# CanhBaoChay.net
KiCad netlist of a schematic drawn in Altium Designer
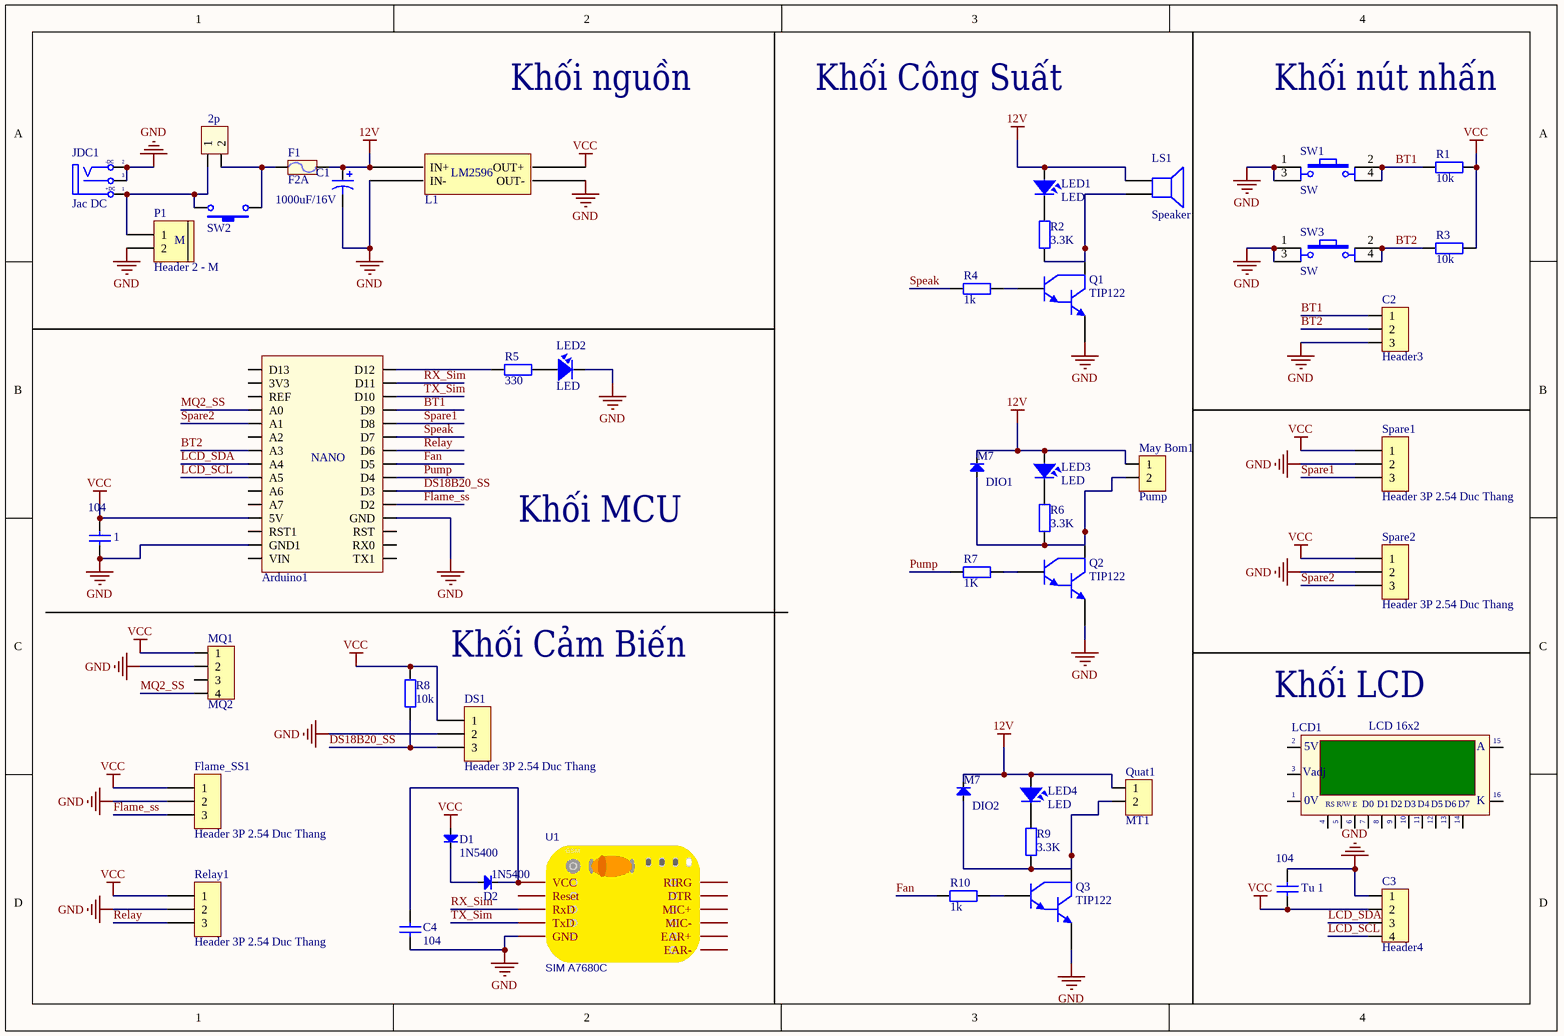
[diagram p0: CanhBaoChay.SchDoc]

(export (version "E")
  (design (tool "Eeschema 10.0.6"))
  (components
    (comp (ref "1")
      (value "104")
      (footprint "C0805")
      (description "Capacitor")
      (fields (field (name "PUBLISHER") "Altium Limited"))
      (libsource (lib "My Library") (part "CapSMD"))
    )
    (comp (ref "Arduino1")
      (value "Arduino Nano")
      (footprint "Arduino Nano")
      (description "Arduino NANO")
      (libsource (lib "My Library") (part "Arduino Nano"))
    )
    (comp (ref "C1")
      (value "1000uF/16V")
      (footprint "C10mm")
      (description "Polarized Capacitor (Axial)")
      (fields (field (name "PUBLISHER") "Altium Limited"))
      (libsource (lib "My Library") (part "Cap Pol 12mm"))
    )
    (comp (ref "C2")
      (value "Header3")
      (footprint "Header3")
      (description "Header IDC, 3 x 1 Pin Vertical 2.54mm Pitch (Non-Boxed, Male)")
      (fields
        (field (name "MANUFACTURER") "Würth Elektronik eiSos GmbH")
        (field (name "PARTNO") "613002143121")
        (field (name "CREATED BY") "Karrer Zheng")
      )
      (libsource (lib "My Library") (part "Header3"))
    )
    (comp (ref "C3")
      (value "Header4")
      (footprint "XH2.54M-4")
      (description "Header IDC, 4 x 1 Pin Vertical 2.54mm Pitch (Non-Boxed, Male)")
      (fields
        (field (name "MANUFACTURER") "Würth Elektronik eiSos GmbH")
        (field (name "PARTNO") "613002143121")
        (field (name "CREATED BY") "Karrer Zheng")
      )
      (libsource (lib "My Library") (part "Header4"))
    )
    (comp (ref "C4")
      (value "104")
      (footprint "C0805")
      (description "Capacitor")
      (fields (field (name "PUBLISHER") "Altium Limited"))
      (libsource (lib "My Library") (part "CapSMD"))
    )
    (comp (ref "D1")
      (value "1N5400")
      (footprint "DIO-5A")
      (description "Default Diode")
      (fields (field (name "PUBLISHER") "Altium Limited"))
      (libsource (lib "My Library") (part "Diode"))
    )
    (comp (ref "D2")
      (value "1N5400")
      (footprint "DIO-5A")
      (description "Default Diode")
      (fields (field (name "PUBLISHER") "Altium Limited"))
      (libsource (lib "My Library") (part "Diode"))
    )
    (comp (ref "DIO1")
      (value "M7")
      (footprint "DIO-SMD-106")
      (description "Default Diode")
      (fields (field (name "PUBLISHER") "Altium Limited"))
      (libsource (lib "My Library (1)") (part "Diode SMD"))
    )
    (comp (ref "DIO2")
      (value "M7")
      (footprint "DIO-SMD-106")
      (description "Default Diode")
      (fields (field (name "PUBLISHER") "Altium Limited"))
      (libsource (lib "My Library (1)") (part "Diode SMD"))
    )
    (comp (ref "DS1")
      (value "Header 3P 2.54 Duc Thang")
      (footprint "Header 3P DC 2.54")
      (description "Cắm")
      (libsource (lib "Header") (part "Header 3P 2.54 Duc Thang"))
    )
    (comp (ref "F1")
      (value "F2A")
      (footprint "Fuse")
      (description "Fuse")
      (fields (field (name "DESIGNED BY") "VanDungEvn"))
      (libsource (lib "My Library") (part "Fuse"))
    )
    (comp (ref "Flame_SS1")
      (value "Header 3P 2.54 Duc Thang")
      (footprint "Header 3P DC 2.54")
      (description "Cắm")
      (libsource (lib "Header") (part "Header 3P 2.54 Duc Thang"))
    )
    (comp (ref "H1")
      (value "2p")
      (footprint "XH2.54M-2")
      (description "Cắm")
      (libsource (lib "Header") (part "Header 2P 2.54 Duc Thang"))
    )
    (comp (ref "JDC1")
      (value "Jac DC")
      (footprint "DC-IN")
      (description "Jac DC input")
      (libsource (lib "My Library") (part "DCIN"))
    )
    (comp (ref "L1")
      (value "BUCK_LM2596")
      (footprint "BUCK_LM2596")
      (libsource (lib "BUCK_LM2596_Sch") (part "BUCK_LM2596"))
    )
    (comp (ref "LCD1")
      (value "LCD 16x2")
      (footprint "LCD16X2N")
      (libsource (lib "My library altium") (part "LCD"))
    )
    (comp (ref "LED1")
      (value "LED")
      (footprint "LED-5 GRe")
      (description "LED Single colour Green and Red")
      (libsource (lib "My Library") (part "LED"))
    )
    (comp (ref "LED2")
      (value "LED")
      (footprint "LED-5 GRe")
      (description "LED Single colour Green and Red")
      (libsource (lib "My Library") (part "LED"))
    )
    (comp (ref "LED3")
      (value "LED")
      (footprint "LED-5 GRe")
      (description "LED Single colour Green and Red")
      (libsource (lib "My Library") (part "LED"))
    )
    (comp (ref "LED4")
      (value "LED")
      (footprint "LED-5 GRe")
      (description "LED Single colour Green and Red")
      (libsource (lib "My Library") (part "LED"))
    )
    (comp (ref "LS1")
      (value "Speaker")
      (footprint "SPEAKER")
      (description "Loudspeaker")
      (fields (field (name "PUBLISHER") "Altium Limited"))
      (libsource (lib "My Library") (part "Speaker"))
    )
    (comp (ref "May Bom1")
      (value "Pump")
      (footprint "Header 2P DC 2.54")
      (description "Header IDC, 2 x 1 Pin Vertical 2.54mm Pitch (Non-Boxed, Male)")
      (fields
        (field (name "MANUFACTURER") "Würth Elektronik eiSos GmbH")
        (field (name "PARTNO") "613002143121")
        (field (name "CREATED BY") "Karrer Zheng")
      )
      (libsource (lib "My Library") (part "Header2"))
    )
    (comp (ref "MQ1")
      (value "MQ2")
      (footprint "Header 4P DC 2.54")
      (description "Header IDC, 4 x 1 Pin Vertical 2.54mm Pitch (Non-Boxed, Male)")
      (fields
        (field (name "MANUFACTURER") "Würth Elektronik eiSos GmbH")
        (field (name "PARTNO") "613002143121")
        (field (name "CREATED BY") "Karrer Zheng")
      )
      (libsource (lib "My Library") (part "Header4"))
    )
    (comp (ref "P1")
      (value "Header 2 - M")
      (footprint "Medium - Header 2")
      (description "Header, 2-Pin, Medium")
      (fields (field (name "PUBLISHER") "Altium Limited"))
      (libsource (lib "My Library") (part "Header 2 - M"))
    )
    (comp (ref "Q1")
      (value "TIP122")
      (footprint "QTO-220")
      (description "Darlington Silicon Power NPN Transistor, 8 Amp, 100 Volts and 65 Watts")
      (libsource (lib "My Library (1)") (part "TIP122"))
    )
    (comp (ref "Q2")
      (value "TIP122")
      (footprint "QTO-220")
      (description "Darlington Silicon Power NPN Transistor, 8 Amp, 100 Volts and 65 Watts")
      (libsource (lib "My Library (1)") (part "TIP122"))
    )
    (comp (ref "Q3")
      (value "TIP122")
      (footprint "QTO-220")
      (description "Darlington Silicon Power NPN Transistor, 8 Amp, 100 Volts and 65 Watts")
      (libsource (lib "My Library (1)") (part "TIP122"))
    )
    (comp (ref "Quat1")
      (value "MT1")
      (footprint "Header 2P DC 2.54")
      (description "Header IDC, 2 x 1 Pin Vertical 2.54mm Pitch (Non-Boxed, Male)")
      (fields
        (field (name "MANUFACTURER") "Würth Elektronik eiSos GmbH")
        (field (name "PARTNO") "613002143121")
        (field (name "CREATED BY") "Karrer Zheng")
      )
      (libsource (lib "My Library") (part "Header2"))
    )
    (comp (ref "R1")
      (value "10k")
      (footprint "RES-SMD-1206")
      (description "Resistor SMD 0805")
      (fields (field (name "PUBLISHER") "Altium Limited"))
      (libsource (lib "") (part "R0805_2"))
    )
    (comp (ref "R2")
      (value "3.3K")
      (footprint "RES-SMD-1206")
      (description "Resistor SMD 0805")
      (fields (field (name "PUBLISHER") "Altium Limited"))
      (libsource (lib "My Library (1)") (part "R0805"))
    )
    (comp (ref "R3")
      (value "10k")
      (footprint "RES-SMD-1206")
      (description "Resistor SMD 0805")
      (fields (field (name "PUBLISHER") "Altium Limited"))
      (libsource (lib "") (part "R0805_2"))
    )
    (comp (ref "R4")
      (value "1k")
      (footprint "RES-SMD-1206")
      (description "Resistor SMD 0805")
      (fields (field (name "PUBLISHER") "Altium Limited"))
      (libsource (lib "") (part "R0805_1"))
    )
    (comp (ref "R5")
      (value "330")
      (footprint "RES-SMD-1206")
      (description "Resistor SMD 0805")
      (fields (field (name "PUBLISHER") "Altium Limited"))
      (libsource (lib "") (part "R0805_1"))
    )
    (comp (ref "R6")
      (value "3.3K")
      (footprint "RES-SMD-1206")
      (description "Resistor SMD 0805")
      (fields (field (name "PUBLISHER") "Altium Limited"))
      (libsource (lib "My Library (1)") (part "R0805"))
    )
    (comp (ref "R7")
      (value "1K")
      (footprint "RES-SMD-1206")
      (description "Resistor SMD 0805")
      (fields (field (name "PUBLISHER") "Altium Limited"))
      (libsource (lib "") (part "R0805_1"))
    )
    (comp (ref "R8")
      (value "10k")
      (footprint "RES-SMD-1206")
      (description "Resistor SMD 0805")
      (fields (field (name "PUBLISHER") "Altium Limited"))
      (libsource (lib "My Library (1)") (part "R0805"))
    )
    (comp (ref "R9")
      (value "3.3K")
      (footprint "RES-SMD-1206")
      (description "Resistor SMD 0805")
      (fields (field (name "PUBLISHER") "Altium Limited"))
      (libsource (lib "My Library (1)") (part "R0805"))
    )
    (comp (ref "R10")
      (value "1k")
      (footprint "RES-SMD-1206")
      (description "Resistor SMD 0805")
      (fields (field (name "PUBLISHER") "Altium Limited"))
      (libsource (lib "") (part "R0805_1"))
    )
    (comp (ref "Relay1")
      (value "Header 3P 2.54 Duc Thang")
      (footprint "XH2.54M-3")
      (description "Cắm")
      (libsource (lib "Header") (part "Header 3P 2.54 Duc Thang"))
    )
    (comp (ref "Spare1")
      (value "Header 3P 2.54 Duc Thang")
      (footprint "XH2.54M-3")
      (description "Cắm")
      (libsource (lib "Header") (part "Header 3P 2.54 Duc Thang"))
    )
    (comp (ref "Spare2")
      (value "Header 3P 2.54 Duc Thang")
      (footprint "XH2.54M-3")
      (description "Cắm")
      (libsource (lib "Header") (part "Header 3P 2.54 Duc Thang"))
    )
    (comp (ref "SW1")
      (value "SW")
      (footprint "SW4")
      (description "Switch button 4 pin")
      (libsource (lib "My Library (1)") (part "SW4"))
    )
    (comp (ref "SW2")
      (value "KCD01-11_SWITCH")
      (footprint "KCD01-11")
      (description "Nut Nhan 2 Chan SMD 3x6x2.5")
      (libsource (lib "KS Chuong") (part "KCD01-11_SWITCH"))
    )
    (comp (ref "SW3")
      (value "SW")
      (footprint "SW4")
      (description "Switch button 4 pin")
      (libsource (lib "My Library (1)") (part "SW4"))
    )
    (comp (ref "Tu 1")
      (value "104")
      (footprint "C0805")
      (description "Capacitor")
      (fields (field (name "PUBLISHER") "Altium Limited"))
      (libsource (lib "My Library") (part "CapSMD"))
    )
    (comp (ref "U1")
      (value "SIM A7680C")
      (footprint "SIM800L MODULE")
      (fields (field (name "BOM_SUPPLIER PART") "B01DLIJM2E") (field (name "CONTRIBUTOR") "trigui"))
      (libsource (lib "Lib_KD") (part "SIM800L"))
    )
  )
  (nets
    (net (code "1") (name "/BT1") (class "Default")
      (node (ref "Arduino1") (pin "D9") (pinfunction "D9_D9") (pintype "passive"))
      (node (ref "C2") (pin "1") (pinfunction "1_1") (pintype "passive"))
      (node (ref "R1") (pin "1") (pinfunction "1_1") (pintype "passive"))
      (node (ref "SW1") (pin "2") (pintype "passive"))
      (node (ref "SW1") (pin "4") (pintype "passive"))
    )
    (net (code "2") (name "/BT2") (class "Default")
      (node (ref "Arduino1") (pin "A3") (pinfunction "A3_A3") (pintype "passive"))
      (node (ref "C2") (pin "2") (pinfunction "2_2") (pintype "passive"))
      (node (ref "R3") (pin "1") (pinfunction "1_1") (pintype "passive"))
      (node (ref "SW3") (pin "2") (pintype "passive"))
      (node (ref "SW3") (pin "4") (pintype "passive"))
    )
    (net (code "3") (name "/DS18B20_SS") (class "Default")
      (node (ref "Arduino1") (pin "D3") (pinfunction "D3_D3") (pintype "passive"))
      (node (ref "DS1") (pin "3") (pinfunction "3_3") (pintype "passive"))
      (node (ref "R8") (pin "2") (pinfunction "2_2") (pintype "passive"))
    )
    (net (code "4") (name "/Fan") (class "Default")
      (node (ref "Arduino1") (pin "D5") (pinfunction "D5_D5") (pintype "passive"))
      (node (ref "R10") (pin "2") (pinfunction "2_2") (pintype "passive"))
    )
    (net (code "5") (name "/Flame_ss") (class "Default")
      (node (ref "Arduino1") (pin "D2") (pinfunction "D2_D2") (pintype "passive"))
      (node (ref "Flame_SS1") (pin "3") (pinfunction "3_3") (pintype "passive"))
    )
    (net (code "6") (name "/LCD_SCL") (class "Default")
      (node (ref "Arduino1") (pin "A5") (pinfunction "A5_A5") (pintype "passive"))
      (node (ref "C3") (pin "4") (pinfunction "4_4") (pintype "passive"))
    )
    (net (code "7") (name "/LCD_SDA") (class "Default")
      (node (ref "Arduino1") (pin "A4") (pinfunction "A4_A4") (pintype "passive"))
      (node (ref "C3") (pin "3") (pinfunction "3_3") (pintype "passive"))
    )
    (net (code "8") (name "/MQ2_SS") (class "Default")
      (node (ref "Arduino1") (pin "A0") (pinfunction "A0_A0") (pintype "passive"))
      (node (ref "MQ1") (pin "4") (pinfunction "4_4") (pintype "passive"))
    )
    (net (code "9") (name "/Pump") (class "Default")
      (node (ref "Arduino1") (pin "D4") (pinfunction "D4_D4") (pintype "passive"))
      (node (ref "R7") (pin "2") (pinfunction "2_2") (pintype "passive"))
    )
    (net (code "10") (name "/RX_Sim") (class "Default")
      (node (ref "Arduino1") (pin "D11") (pinfunction "D11_D11") (pintype "passive"))
      (node (ref "U1") (pin "3") (pinfunction "RxD_3") (pintype "passive"))
    )
    (net (code "11") (name "/Relay") (class "Default")
      (node (ref "Arduino1") (pin "D6") (pinfunction "D6_D6") (pintype "passive"))
      (node (ref "Relay1") (pin "3") (pinfunction "3_3") (pintype "passive"))
    )
    (net (code "12") (name "/Spare1") (class "Default")
      (node (ref "Arduino1") (pin "D8") (pinfunction "D8_D8") (pintype "passive"))
      (node (ref "Spare1") (pin "3") (pinfunction "3_3") (pintype "passive"))
    )
    (net (code "13") (name "/Spare2") (class "Default")
      (node (ref "Arduino1") (pin "A1") (pinfunction "A1_A1") (pintype "passive"))
      (node (ref "Spare2") (pin "3") (pinfunction "3_3") (pintype "passive"))
    )
    (net (code "14") (name "/Speak") (class "Default")
      (node (ref "Arduino1") (pin "D7") (pinfunction "D7_D7") (pintype "passive"))
      (node (ref "R4") (pin "2") (pinfunction "2_2") (pintype "passive"))
    )
    (net (code "15") (name "/TX_Sim") (class "Default")
      (node (ref "Arduino1") (pin "D10") (pinfunction "D10_D10") (pintype "passive"))
      (node (ref "U1") (pin "4") (pinfunction "TxD_4") (pintype "passive"))
    )
    (net (code "16") (name "12V") (class "Default")
      (node (ref "C1") (pin "1") (pinfunction "1_1") (pintype "passive"))
      (node (ref "DIO1") (pin "2") (pinfunction "K_2") (pintype "passive"))
      (node (ref "DIO2") (pin "2") (pinfunction "K_2") (pintype "passive"))
      (node (ref "F1") (pin "2") (pinfunction "2_2") (pintype "passive"))
      (node (ref "L1") (pin "1") (pinfunction "IN+_1") (pintype "passive"))
      (node (ref "LED1") (pin "1") (pinfunction "1_1") (pintype "passive"))
      (node (ref "LED3") (pin "1") (pinfunction "1_1") (pintype "passive"))
      (node (ref "LED4") (pin "1") (pinfunction "1_1") (pintype "passive"))
      (node (ref "LS1") (pin "1") (pinfunction "1_1") (pintype "passive"))
      (node (ref "May Bom1") (pin "1") (pinfunction "1_1") (pintype "passive"))
      (node (ref "Quat1") (pin "1") (pinfunction "1_1") (pintype "passive"))
    )
    (net (code "17") (name "GND") (class "Default")
      (node (ref "1") (pin "1") (pinfunction "1_1") (pintype "passive"))
      (node (ref "Arduino1") (pin "GND") (pinfunction "GND_GND") (pintype "passive"))
      (node (ref "Arduino1") (pin "GND1") (pinfunction "GND1_GND1") (pintype "passive"))
      (node (ref "C1") (pin "2") (pinfunction "2_2") (pintype "passive"))
      (node (ref "C2") (pin "3") (pinfunction "3_3") (pintype "passive"))
      (node (ref "C3") (pin "1") (pinfunction "1_1") (pintype "passive"))
      (node (ref "C4") (pin "2") (pinfunction "2_2") (pintype "passive"))
      (node (ref "DS1") (pin "2") (pinfunction "2_2") (pintype "passive"))
      (node (ref "Flame_SS1") (pin "2") (pinfunction "2_2") (pintype "passive"))
      (node (ref "JDC1") (pin "2") (pinfunction "TN_2") (pintype "passive"))
      (node (ref "JDC1") (pin "3") (pinfunction "S_3") (pintype "power_in"))
      (node (ref "L1") (pin "2") (pinfunction "IN-_2") (pintype "passive"))
      (node (ref "L1") (pin "3") (pinfunction "OUT-_3") (pintype "passive"))
      (node (ref "LED2") (pin "2") (pinfunction "2_2") (pintype "passive"))
      (node (ref "MQ1") (pin "2") (pinfunction "2_2") (pintype "passive"))
      (node (ref "P1") (pin "2") (pinfunction "2_2") (pintype "passive"))
      (node (ref "Q1") (pin "3") (pinfunction "E_3") (pintype "passive"))
      (node (ref "Q2") (pin "3") (pinfunction "E_3") (pintype "passive"))
      (node (ref "Q3") (pin "3") (pinfunction "E_3") (pintype "passive"))
      (node (ref "Relay1") (pin "2") (pinfunction "2_2") (pintype "passive"))
      (node (ref "SW1") (pin "1") (pintype "passive"))
      (node (ref "SW1") (pin "3") (pintype "passive"))
      (node (ref "SW3") (pin "1") (pintype "passive"))
      (node (ref "SW3") (pin "3") (pintype "passive"))
      (node (ref "Spare1") (pin "2") (pinfunction "2_2") (pintype "passive"))
      (node (ref "Spare2") (pin "2") (pinfunction "2_2") (pintype "passive"))
      (node (ref "Tu 1") (pin "2") (pinfunction "2_2") (pintype "passive"))
      (node (ref "U1") (pin "5") (pinfunction "GND_5") (pintype "passive"))
    )
    (net (code "18") (name "Net-(Arduino1-PadD12)") (class "Default")
      (node (ref "Arduino1") (pin "D12") (pinfunction "D12_D12") (pintype "passive"))
      (node (ref "R5") (pin "2") (pinfunction "2_2") (pintype "passive"))
    )
    (net (code "19") (name "Net-(D1-K)") (class "Default")
      (node (ref "D1") (pin "2") (pinfunction "K_2") (pintype "passive"))
      (node (ref "D2") (pin "1") (pinfunction "A_1") (pintype "passive"))
    )
    (net (code "20") (name "Net-(D2-K)") (class "Default")
      (node (ref "C4") (pin "1") (pinfunction "1_1") (pintype "passive"))
      (node (ref "D2") (pin "2") (pinfunction "K_2") (pintype "passive"))
      (node (ref "U1") (pin "1") (pinfunction "VCC_1") (pintype "passive"))
    )
    (net (code "21") (name "Net-(DIO1-A)") (class "Default")
      (node (ref "DIO1") (pin "1") (pinfunction "A_1") (pintype "passive"))
      (node (ref "May Bom1") (pin "2") (pinfunction "2_2") (pintype "passive"))
      (node (ref "Q2") (pin "2") (pinfunction "C_2") (pintype "passive"))
      (node (ref "R6") (pin "2") (pinfunction "2_2") (pintype "passive"))
    )
    (net (code "22") (name "Net-(DIO2-A)") (class "Default")
      (node (ref "DIO2") (pin "1") (pinfunction "A_1") (pintype "passive"))
      (node (ref "Q3") (pin "2") (pinfunction "C_2") (pintype "passive"))
      (node (ref "Quat1") (pin "2") (pinfunction "2_2") (pintype "passive"))
      (node (ref "R9") (pin "2") (pinfunction "2_2") (pintype "passive"))
    )
    (net (code "23") (name "Net-(F1-Pad1)") (class "Default")
      (node (ref "F1") (pin "1") (pinfunction "1_1") (pintype "passive"))
      (node (ref "H1") (pin "2") (pinfunction "2_2") (pintype "passive"))
      (node (ref "SW2") (pin "1") (pinfunction "1_1") (pintype "passive"))
    )
    (net (code "24") (name "Net-(JDC1-T)") (class "Default")
      (node (ref "H1") (pin "1") (pinfunction "1_1") (pintype "passive"))
      (node (ref "JDC1") (pin "1") (pinfunction "T_1") (pintype "passive"))
      (node (ref "P1") (pin "1") (pinfunction "1_1") (pintype "passive"))
      (node (ref "SW2") (pin "2") (pinfunction "2_2") (pintype "passive"))
    )
    (net (code "25") (name "Net-(LED1-Pad2)") (class "Default")
      (node (ref "LED1") (pin "2") (pinfunction "2_2") (pintype "passive"))
      (node (ref "R2") (pin "1") (pinfunction "1_1") (pintype "passive"))
    )
    (net (code "26") (name "Net-(LED2-Pad1)") (class "Default")
      (node (ref "LED2") (pin "1") (pinfunction "1_1") (pintype "passive"))
      (node (ref "R5") (pin "1") (pinfunction "1_1") (pintype "passive"))
    )
    (net (code "27") (name "Net-(LED3-Pad2)") (class "Default")
      (node (ref "LED3") (pin "2") (pinfunction "2_2") (pintype "passive"))
      (node (ref "R6") (pin "1") (pinfunction "1_1") (pintype "passive"))
    )
    (net (code "28") (name "Net-(LED4-Pad2)") (class "Default")
      (node (ref "LED4") (pin "2") (pinfunction "2_2") (pintype "passive"))
      (node (ref "R9") (pin "1") (pinfunction "1_1") (pintype "passive"))
    )
    (net (code "29") (name "Net-(Q1-B)") (class "Default")
      (node (ref "Q1") (pin "1") (pinfunction "B_1") (pintype "passive"))
      (node (ref "R4") (pin "1") (pinfunction "1_1") (pintype "passive"))
    )
    (net (code "30") (name "Net-(Q1-C)") (class "Default")
      (node (ref "LS1") (pin "2") (pinfunction "2_2") (pintype "passive"))
      (node (ref "Q1") (pin "2") (pinfunction "C_2") (pintype "passive"))
      (node (ref "R2") (pin "2") (pinfunction "2_2") (pintype "passive"))
    )
    (net (code "31") (name "Net-(Q2-B)") (class "Default")
      (node (ref "Q2") (pin "1") (pinfunction "B_1") (pintype "passive"))
      (node (ref "R7") (pin "1") (pinfunction "1_1") (pintype "passive"))
    )
    (net (code "32") (name "Net-(Q3-B)") (class "Default")
      (node (ref "Q3") (pin "1") (pinfunction "B_1") (pintype "passive"))
      (node (ref "R10") (pin "1") (pinfunction "1_1") (pintype "passive"))
    )
    (net (code "33") (name "VCC") (class "Default")
      (node (ref "1") (pin "2") (pinfunction "2_2") (pintype "passive"))
      (node (ref "Arduino1") (pin "5V") (pinfunction "5V_5V") (pintype "passive"))
      (node (ref "C3") (pin "2") (pinfunction "2_2") (pintype "passive"))
      (node (ref "D1") (pin "1") (pinfunction "A_1") (pintype "passive"))
      (node (ref "DS1") (pin "1") (pinfunction "1_1") (pintype "passive"))
      (node (ref "Flame_SS1") (pin "1") (pinfunction "1_1") (pintype "passive"))
      (node (ref "L1") (pin "4") (pinfunction "OUT+_4") (pintype "passive"))
      (node (ref "MQ1") (pin "1") (pinfunction "1_1") (pintype "passive"))
      (node (ref "R1") (pin "2") (pinfunction "2_2") (pintype "passive"))
      (node (ref "R3") (pin "2") (pinfunction "2_2") (pintype "passive"))
      (node (ref "R8") (pin "1") (pinfunction "1_1") (pintype "passive"))
      (node (ref "Relay1") (pin "1") (pinfunction "1_1") (pintype "passive"))
      (node (ref "Spare1") (pin "1") (pinfunction "1_1") (pintype "passive"))
      (node (ref "Spare2") (pin "1") (pinfunction "1_1") (pintype "passive"))
      (node (ref "Tu 1") (pin "1") (pinfunction "1_1") (pintype "passive"))
    )
    (net (code "34") (name "unconnected-(Arduino1-Pad3V3)") (class "Default")
      (node (ref "Arduino1") (pin "3V3") (pinfunction "3V3_3V3") (pintype "passive"))
    )
    (net (code "35") (name "unconnected-(Arduino1-PadA2)") (class "Default")
      (node (ref "Arduino1") (pin "A2") (pinfunction "A2_A2") (pintype "passive"))
    )
    (net (code "36") (name "unconnected-(Arduino1-PadA6)") (class "Default")
      (node (ref "Arduino1") (pin "A6") (pinfunction "A6_A6") (pintype "passive"))
    )
    (net (code "37") (name "unconnected-(Arduino1-PadA7)") (class "Default")
      (node (ref "Arduino1") (pin "A7") (pinfunction "A7_A7") (pintype "passive"))
    )
    (net (code "38") (name "unconnected-(Arduino1-PadD13)") (class "Default")
      (node (ref "Arduino1") (pin "D13") (pinfunction "D13_D13") (pintype "passive"))
    )
    (net (code "39") (name "unconnected-(Arduino1-PadREF)") (class "Default")
      (node (ref "Arduino1") (pin "REF") (pinfunction "REF_REF") (pintype "passive"))
    )
    (net (code "40") (name "unconnected-(Arduino1-PadRST)") (class "Default")
      (node (ref "Arduino1") (pin "RST") (pinfunction "RST_RST") (pintype "passive"))
    )
    (net (code "41") (name "unconnected-(Arduino1-PadRST1)") (class "Default")
      (node (ref "Arduino1") (pin "RST1") (pinfunction "RST1_RST1") (pintype "passive"))
    )
    (net (code "42") (name "unconnected-(Arduino1-PadRX0)") (class "Default")
      (node (ref "Arduino1") (pin "RX0") (pinfunction "RX0_RX0") (pintype "passive"))
    )
    (net (code "43") (name "unconnected-(Arduino1-PadTX1)") (class "Default")
      (node (ref "Arduino1") (pin "TX1") (pinfunction "TX1_TX1") (pintype "passive"))
    )
    (net (code "44") (name "unconnected-(Arduino1-PadVIN)") (class "Default")
      (node (ref "Arduino1") (pin "VIN") (pinfunction "VIN_VIN") (pintype "passive"))
    )
    (net (code "45") (name "unconnected-(LCD1-A-Pad15)") (class "Default")
      (node (ref "LCD1") (pin "15") (pinfunction "A_15") (pintype "passive"))
    )
    (net (code "46") (name "unconnected-(LCD1-D0-Pad7)") (class "Default")
      (node (ref "LCD1") (pin "7") (pinfunction "D0_7") (pintype "passive"))
    )
    (net (code "47") (name "unconnected-(LCD1-D1-Pad8)") (class "Default")
      (node (ref "LCD1") (pin "8") (pinfunction "D1_8") (pintype "passive"))
    )
    (net (code "48") (name "unconnected-(LCD1-D2-Pad9)") (class "Default")
      (node (ref "LCD1") (pin "9") (pinfunction "D2_9") (pintype "passive"))
    )
    (net (code "49") (name "unconnected-(LCD1-D3-Pad10)") (class "Default")
      (node (ref "LCD1") (pin "10") (pinfunction "D3_10") (pintype "passive"))
    )
    (net (code "50") (name "unconnected-(LCD1-D4-Pad11)") (class "Default")
      (node (ref "LCD1") (pin "11") (pinfunction "D4_11") (pintype "passive"))
    )
    (net (code "51") (name "unconnected-(LCD1-D5-Pad12)") (class "Default")
      (node (ref "LCD1") (pin "12") (pinfunction "D5_12") (pintype "passive"))
    )
    (net (code "52") (name "unconnected-(LCD1-D6-Pad13)") (class "Default")
      (node (ref "LCD1") (pin "13") (pinfunction "D6_13") (pintype "passive"))
    )
    (net (code "53") (name "unconnected-(LCD1-D7-Pad14)") (class "Default")
      (node (ref "LCD1") (pin "14") (pinfunction "D7_14") (pintype "passive"))
    )
    (net (code "54") (name "unconnected-(LCD1-GND-Pad1)") (class "Default")
      (node (ref "LCD1") (pin "1") (pinfunction "GND_1") (pintype "passive"))
    )
    (net (code "55") (name "unconnected-(LCD1-K-Pad16)") (class "Default")
      (node (ref "LCD1") (pin "16") (pinfunction "K_16") (pintype "passive"))
    )
    (net (code "56") (name "unconnected-(LCD1-RS-Pad4)") (class "Default")
      (node (ref "LCD1") (pin "4") (pinfunction "RS_4") (pintype "passive"))
    )
    (net (code "57") (name "unconnected-(LCD1-R{slash}~{W}-Pad5)") (class "Default")
      (node (ref "LCD1") (pin "5") (pinfunction "R/~{W}_5") (pintype "passive"))
    )
    (net (code "58") (name "unconnected-(LCD1-VAdj-Pad3)") (class "Default")
      (node (ref "LCD1") (pin "3") (pinfunction "VAdj_3") (pintype "passive"))
    )
    (net (code "59") (name "unconnected-(LCD1-VDD-Pad2)") (class "Default")
      (node (ref "LCD1") (pin "2") (pinfunction "VDD_2") (pintype "passive"))
    )
    (net (code "60") (name "unconnected-(LCD1-~{EN}-Pad6)") (class "Default")
      (node (ref "LCD1") (pin "6") (pinfunction "~{EN}_6") (pintype "passive"))
    )
    (net (code "61") (name "unconnected-(MQ1-Pad3)") (class "Default")
      (node (ref "MQ1") (pin "3") (pinfunction "3_3") (pintype "passive"))
    )
    (net (code "62") (name "unconnected-(U1-DTR-Pad7)") (class "Default")
      (node (ref "U1") (pin "7") (pinfunction "DTR_7") (pintype "passive"))
    )
    (net (code "63") (name "unconnected-(U1-EAR+-Pad10)") (class "Default")
      (node (ref "U1") (pin "10") (pinfunction "EAR+_10") (pintype "passive"))
    )
    (net (code "64") (name "unconnected-(U1-EAR--Pad11)") (class "Default")
      (node (ref "U1") (pin "11") (pinfunction "EAR-_11") (pintype "passive"))
    )
    (net (code "65") (name "unconnected-(U1-MIC+-Pad8)") (class "Default")
      (node (ref "U1") (pin "8") (pinfunction "MIC+_8") (pintype "passive"))
    )
    (net (code "66") (name "unconnected-(U1-MIC--Pad9)") (class "Default")
      (node (ref "U1") (pin "9") (pinfunction "MIC-_9") (pintype "passive"))
    )
    (net (code "67") (name "unconnected-(U1-RIRG-Pad6)") (class "Default")
      (node (ref "U1") (pin "6") (pinfunction "RIRG_6") (pintype "passive"))
    )
    (net (code "68") (name "unconnected-(U1-Reset-Pad2)") (class "Default")
      (node (ref "U1") (pin "2") (pinfunction "Reset_2") (pintype "passive"))
    )
  )
)
